# M307.net
KiCad netlist of a schematic drawn in EAGLE
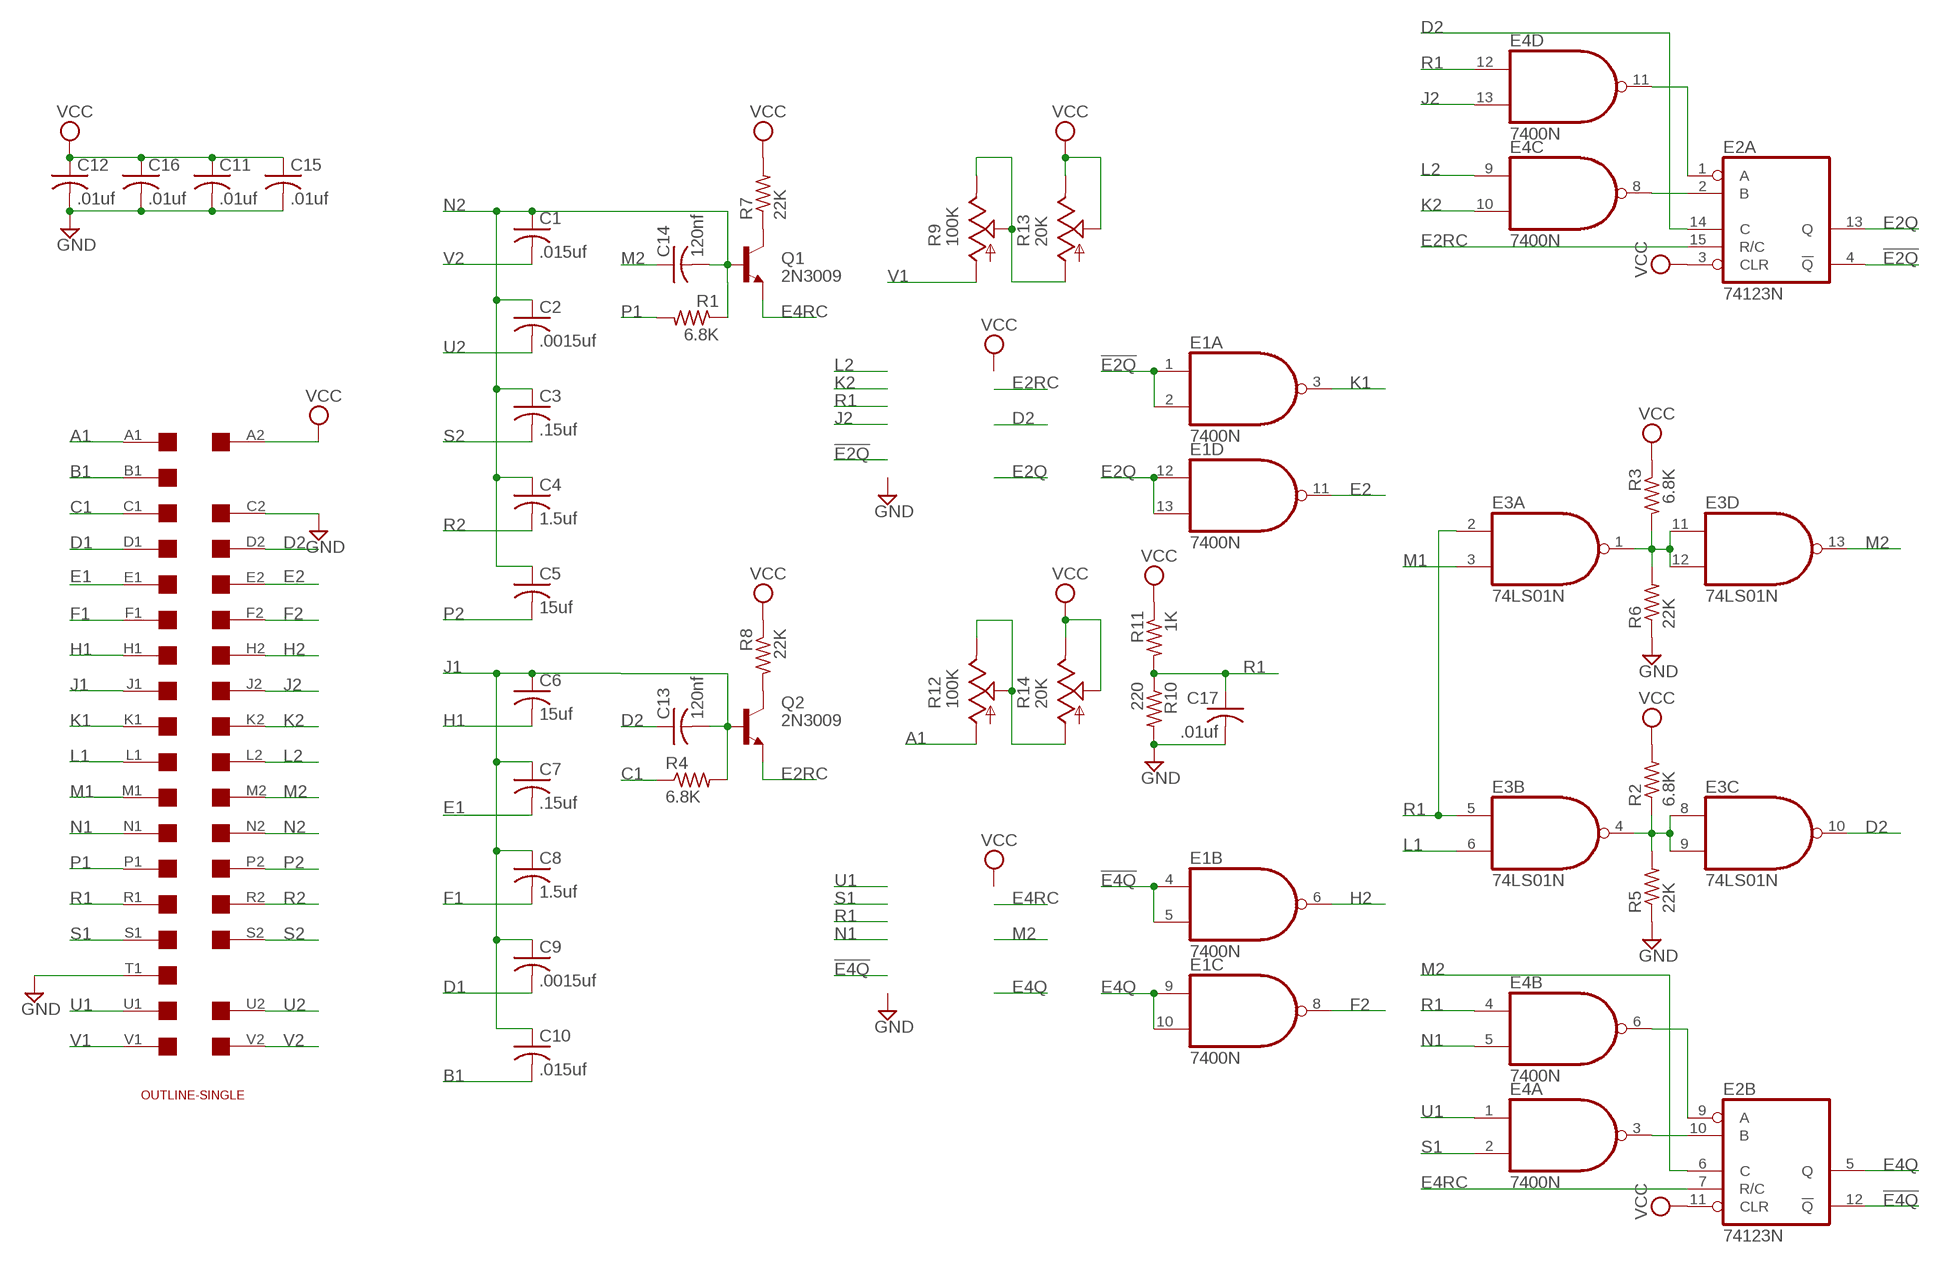
[diagram p0: schematic, sheet 1]

(export (version "E")
  (design (tool "Eeschema 10.0.6"))
  (components
    (comp (ref "C1")
      (value ".015uf")
      (footprint "eagle-import:C150-054X183")
      (libsource (lib "eagle-import") (part "C-US150-054X183"))
    )
    (comp (ref "C2")
      (value ".0015uf")
      (footprint "eagle-import:C050-025X075")
      (libsource (lib "eagle-import") (part "C-US050-025X075"))
    )
    (comp (ref "C3")
      (value ".15uf")
      (footprint "eagle-import:C102-043X133")
      (libsource (lib "eagle-import") (part "C-US102-043X133"))
    )
    (comp (ref "C4")
      (value "1.5uf")
      (footprint "eagle-import:C150-054X183")
      (libsource (lib "eagle-import") (part "C-US150-054X183"))
    )
    (comp (ref "C5")
      (value "15uf")
      (footprint "eagle-import:C150-054X183")
      (libsource (lib "eagle-import") (part "C-US150-054X183"))
    )
    (comp (ref "C6")
      (value "15uf")
      (footprint "eagle-import:C150-054X183")
      (libsource (lib "eagle-import") (part "C-US150-054X183"))
    )
    (comp (ref "C7")
      (value ".15uf")
      (footprint "eagle-import:C102-043X133")
      (libsource (lib "eagle-import") (part "C-US102-043X133"))
    )
    (comp (ref "C8")
      (value "1.5uf")
      (footprint "eagle-import:C150-054X183")
      (libsource (lib "eagle-import") (part "C-US150-054X183"))
    )
    (comp (ref "C9")
      (value ".0015uf")
      (footprint "eagle-import:C050-025X075")
      (libsource (lib "eagle-import") (part "C-US050-025X075"))
    )
    (comp (ref "C10")
      (value ".015uf")
      (footprint "eagle-import:C150-054X183")
      (libsource (lib "eagle-import") (part "C-US150-054X183"))
    )
    (comp (ref "C11")
      (value ".01uf")
      (footprint "eagle-import:C050-025X075")
      (libsource (lib "eagle-import") (part "C-US050-025X075"))
    )
    (comp (ref "C12")
      (value ".01uf")
      (footprint "eagle-import:C050-025X075")
      (libsource (lib "eagle-import") (part "C-US050-025X075"))
    )
    (comp (ref "C13")
      (value "120nf")
      (footprint "eagle-import:C075-032X103")
      (libsource (lib "eagle-import") (part "C-US075-032X103"))
    )
    (comp (ref "C14")
      (value "120nf")
      (footprint "eagle-import:C075-032X103")
      (libsource (lib "eagle-import") (part "C-US075-032X103"))
    )
    (comp (ref "C15")
      (value ".01uf")
      (footprint "eagle-import:C050-025X075")
      (libsource (lib "eagle-import") (part "C-US050-025X075"))
    )
    (comp (ref "C16")
      (value ".01uf")
      (footprint "eagle-import:C050-025X075")
      (libsource (lib "eagle-import") (part "C-US050-025X075"))
    )
    (comp (ref "C17")
      (value ".01uf")
      (footprint "eagle-import:C050-025X075")
      (libsource (lib "eagle-import") (part "C-US050-025X075"))
    )
    (comp (ref "E1")
      (value "7400N")
      (footprint "eagle-import:DIL14")
      (libsource (lib "eagle-import") (part "7400N"))
    )
    (comp (ref "E2")
      (value "74123N")
      (footprint "eagle-import:DIL16")
      (libsource (lib "eagle-import") (part "74123N"))
    )
    (comp (ref "E3")
      (value "74LS01N")
      (footprint "eagle-import:DIL14")
      (libsource (lib "eagle-import") (part "7401NLS"))
    )
    (comp (ref "E4")
      (value "7400N")
      (footprint "eagle-import:DIL14")
      (libsource (lib "eagle-import") (part "7400N"))
    )
    (comp (ref "Q1")
      (value "2N3009")
      (footprint "eagle-import:TO39")
      (libsource (lib "eagle-import") (part "-NPN-TO39-EBC2N3019"))
    )
    (comp (ref "Q2")
      (value "2N3009")
      (footprint "eagle-import:TO39")
      (libsource (lib "eagle-import") (part "-NPN-TO39-EBC2N3019"))
    )
    (comp (ref "R1")
      (value "6.8K")
      (footprint "eagle-import:0207_10")
      (libsource (lib "eagle-import") (part "R-US_0207/10"))
    )
    (comp (ref "R2")
      (value "6.8K")
      (footprint "eagle-import:0207_10")
      (libsource (lib "eagle-import") (part "R-US_0207/10"))
    )
    (comp (ref "R3")
      (value "6.8K")
      (footprint "eagle-import:0207_10")
      (libsource (lib "eagle-import") (part "R-US_0207/10"))
    )
    (comp (ref "R4")
      (value "6.8K")
      (footprint "eagle-import:0207_10")
      (libsource (lib "eagle-import") (part "R-US_0207/10"))
    )
    (comp (ref "R5")
      (value "22K")
      (footprint "eagle-import:0207_10")
      (libsource (lib "eagle-import") (part "R-US_0207/10"))
    )
    (comp (ref "R6")
      (value "22K")
      (footprint "eagle-import:0207_10")
      (libsource (lib "eagle-import") (part "R-US_0207/10"))
    )
    (comp (ref "R7")
      (value "22K")
      (footprint "eagle-import:0207_10")
      (libsource (lib "eagle-import") (part "R-US_0207/10"))
    )
    (comp (ref "R8")
      (value "22K")
      (footprint "eagle-import:0207_10")
      (libsource (lib "eagle-import") (part "R-US_0207/10"))
    )
    (comp (ref "R9")
      (value "100K")
      (footprint "eagle-import:PT-SPIN")
      (libsource (lib "eagle-import") (part "TRIM_US-PTSPIN"))
    )
    (comp (ref "R10")
      (value "220")
      (footprint "eagle-import:0207_10")
      (libsource (lib "eagle-import") (part "R-US_0207/10"))
    )
    (comp (ref "R11")
      (value "1K")
      (footprint "eagle-import:0207_10")
      (libsource (lib "eagle-import") (part "R-US_0207/10"))
    )
    (comp (ref "R12")
      (value "100K")
      (footprint "eagle-import:PT-SPIN")
      (libsource (lib "eagle-import") (part "TRIM_US-PTSPIN"))
    )
    (comp (ref "R13")
      (value "20K")
      (footprint "eagle-import:PT-SPIN")
      (libsource (lib "eagle-import") (part "TRIM_US-PTSPIN"))
    )
    (comp (ref "R14")
      (value "20K")
      (footprint "eagle-import:PT-SPIN")
      (libsource (lib "eagle-import") (part "TRIM_US-PTSPIN"))
    )
    (comp (ref "U$1")
      (value "SINGLE")
      (footprint "eagle-import:EDGE-CON2")
      (libsource (lib "eagle-import") (part "SINGLE"))
    )
    (comp (ref "U$4")
      (value "OUTLINE-SINGLE")
      (footprint "eagle-import:SINGLE")
      (libsource (lib "eagle-import") (part "OUTLINE-SINGLE"))
    )
  )
  (nets
    (net (code "1") (name "/A1") (class "Default")
      (node (ref "R12") (pin "A") (pinfunction "A_A") (pintype "passive"))
      (node (ref "U$1") (pin "A1") (pinfunction "1_A1") (pintype "bidirectional"))
    )
    (net (code "2") (name "/B1") (class "Default")
      (node (ref "C10") (pin "2") (pinfunction "2_2") (pintype "passive"))
      (node (ref "U$1") (pin "B1") (pinfunction "1_B1") (pintype "bidirectional"))
    )
    (net (code "3") (name "/C1") (class "Default")
      (node (ref "R4") (pin "1") (pinfunction "1_1") (pintype "passive"))
      (node (ref "U$1") (pin "C1") (pinfunction "1_C1") (pintype "bidirectional"))
    )
    (net (code "4") (name "/D1") (class "Default")
      (node (ref "C9") (pin "2") (pinfunction "2_2") (pintype "passive"))
      (node (ref "U$1") (pin "D1") (pinfunction "1_D1") (pintype "bidirectional"))
    )
    (net (code "5") (name "/D2") (class "Default")
      (node (ref "C13") (pin "1") (pinfunction "1_1") (pintype "passive"))
      (node (ref "E2") (pin "14") (pinfunction "C_14") (pintype "input"))
      (node (ref "E3") (pin "10") (pinfunction "O_10") (pintype "open_collector"))
      (node (ref "U$1") (pin "D2") (pinfunction "1_D2") (pintype "bidirectional"))
    )
    (net (code "6") (name "/E1") (class "Default")
      (node (ref "C7") (pin "2") (pinfunction "2_2") (pintype "passive"))
      (node (ref "U$1") (pin "E1") (pinfunction "1_E1") (pintype "bidirectional"))
    )
    (net (code "7") (name "/E2") (class "Default")
      (node (ref "E1") (pin "11") (pinfunction "O_11") (pintype "output"))
      (node (ref "U$1") (pin "E2") (pinfunction "1_E2") (pintype "bidirectional"))
    )
    (net (code "8") (name "/E2Q") (class "Default")
      (node (ref "E1") (pin "12") (pinfunction "I0_12") (pintype "input"))
      (node (ref "E1") (pin "13") (pinfunction "I1_13") (pintype "input"))
      (node (ref "E2") (pin "13") (pinfunction "Q_13") (pintype "output"))
    )
    (net (code "9") (name "/E2RC") (class "Default")
      (node (ref "E2") (pin "15") (pinfunction "R/C_15") (pintype "input"))
      (node (ref "Q2") (pin "1") (pinfunction "E_1") (pintype "passive"))
    )
    (net (code "10") (name "/E4Q") (class "Default")
      (node (ref "E1") (pin "10") (pinfunction "I1_10") (pintype "input"))
      (node (ref "E1") (pin "9") (pinfunction "I0_9") (pintype "input"))
      (node (ref "E2") (pin "5") (pinfunction "Q_5") (pintype "output"))
    )
    (net (code "11") (name "/E4RC") (class "Default")
      (node (ref "E2") (pin "7") (pinfunction "R/C_7") (pintype "input"))
      (node (ref "Q1") (pin "1") (pinfunction "E_1") (pintype "passive"))
    )
    (net (code "12") (name "/F1") (class "Default")
      (node (ref "C8") (pin "2") (pinfunction "2_2") (pintype "passive"))
      (node (ref "U$1") (pin "F1") (pinfunction "1_F1") (pintype "bidirectional"))
    )
    (net (code "13") (name "/F2") (class "Default")
      (node (ref "E1") (pin "8") (pinfunction "O_8") (pintype "output"))
      (node (ref "U$1") (pin "F2") (pinfunction "1_F2") (pintype "bidirectional"))
    )
    (net (code "14") (name "/H1") (class "Default")
      (node (ref "C6") (pin "2") (pinfunction "2_2") (pintype "passive"))
      (node (ref "U$1") (pin "H1") (pinfunction "1_H1") (pintype "bidirectional"))
    )
    (net (code "15") (name "/H2") (class "Default")
      (node (ref "E1") (pin "6") (pinfunction "O_6") (pintype "output"))
      (node (ref "U$1") (pin "H2") (pinfunction "1_H2") (pintype "bidirectional"))
    )
    (net (code "16") (name "/J1") (class "Default")
      (node (ref "C10") (pin "1") (pinfunction "1_1") (pintype "passive"))
      (node (ref "C13") (pin "2") (pinfunction "2_2") (pintype "passive"))
      (node (ref "C6") (pin "1") (pinfunction "1_1") (pintype "passive"))
      (node (ref "C7") (pin "1") (pinfunction "1_1") (pintype "passive"))
      (node (ref "C8") (pin "1") (pinfunction "1_1") (pintype "passive"))
      (node (ref "C9") (pin "1") (pinfunction "1_1") (pintype "passive"))
      (node (ref "Q2") (pin "2") (pinfunction "B_2") (pintype "passive"))
      (node (ref "R4") (pin "2") (pinfunction "2_2") (pintype "passive"))
      (node (ref "U$1") (pin "J1") (pinfunction "1_J1") (pintype "bidirectional"))
    )
    (net (code "17") (name "/J2") (class "Default")
      (node (ref "E4") (pin "13") (pinfunction "I1_13") (pintype "input"))
      (node (ref "U$1") (pin "J2") (pinfunction "1_J2") (pintype "bidirectional"))
    )
    (net (code "18") (name "/K1") (class "Default")
      (node (ref "E1") (pin "3") (pinfunction "O_3") (pintype "output"))
      (node (ref "U$1") (pin "K1") (pinfunction "1_K1") (pintype "bidirectional"))
    )
    (net (code "19") (name "/K2") (class "Default")
      (node (ref "E4") (pin "10") (pinfunction "I1_10") (pintype "input"))
      (node (ref "U$1") (pin "K2") (pinfunction "1_K2") (pintype "bidirectional"))
    )
    (net (code "20") (name "/L1") (class "Default")
      (node (ref "E3") (pin "6") (pinfunction "I1_6") (pintype "input"))
      (node (ref "U$1") (pin "L1") (pinfunction "1_L1") (pintype "bidirectional"))
    )
    (net (code "21") (name "/L2") (class "Default")
      (node (ref "E4") (pin "9") (pinfunction "I0_9") (pintype "input"))
      (node (ref "U$1") (pin "L2") (pinfunction "1_L2") (pintype "bidirectional"))
    )
    (net (code "22") (name "/M1") (class "Default")
      (node (ref "E3") (pin "3") (pinfunction "I1_3") (pintype "input"))
      (node (ref "U$1") (pin "M1") (pinfunction "1_M1") (pintype "bidirectional"))
    )
    (net (code "23") (name "/M2") (class "Default")
      (node (ref "C14") (pin "1") (pinfunction "1_1") (pintype "passive"))
      (node (ref "E2") (pin "6") (pinfunction "C_6") (pintype "input"))
      (node (ref "E3") (pin "13") (pinfunction "O_13") (pintype "open_collector"))
      (node (ref "U$1") (pin "M2") (pinfunction "1_M2") (pintype "bidirectional"))
    )
    (net (code "24") (name "/N1") (class "Default")
      (node (ref "E4") (pin "5") (pinfunction "I1_5") (pintype "input"))
      (node (ref "U$1") (pin "N1") (pinfunction "1_N1") (pintype "bidirectional"))
    )
    (net (code "25") (name "/N2") (class "Default")
      (node (ref "C1") (pin "1") (pinfunction "1_1") (pintype "passive"))
      (node (ref "C14") (pin "2") (pinfunction "2_2") (pintype "passive"))
      (node (ref "C2") (pin "1") (pinfunction "1_1") (pintype "passive"))
      (node (ref "C3") (pin "1") (pinfunction "1_1") (pintype "passive"))
      (node (ref "C4") (pin "1") (pinfunction "1_1") (pintype "passive"))
      (node (ref "C5") (pin "1") (pinfunction "1_1") (pintype "passive"))
      (node (ref "Q1") (pin "2") (pinfunction "B_2") (pintype "passive"))
      (node (ref "R1") (pin "1") (pinfunction "1_1") (pintype "passive"))
      (node (ref "U$1") (pin "N2") (pinfunction "1_N2") (pintype "bidirectional"))
    )
    (net (code "26") (name "/P1") (class "Default")
      (node (ref "R1") (pin "2") (pinfunction "2_2") (pintype "passive"))
      (node (ref "U$1") (pin "P1") (pinfunction "1_P1") (pintype "bidirectional"))
    )
    (net (code "27") (name "/P2") (class "Default")
      (node (ref "C5") (pin "2") (pinfunction "2_2") (pintype "passive"))
      (node (ref "U$1") (pin "P2") (pinfunction "1_P2") (pintype "bidirectional"))
    )
    (net (code "28") (name "/R1") (class "Default")
      (node (ref "C17") (pin "1") (pinfunction "1_1") (pintype "passive"))
      (node (ref "E3") (pin "2") (pinfunction "I0_2") (pintype "input"))
      (node (ref "E3") (pin "5") (pinfunction "I0_5") (pintype "input"))
      (node (ref "E4") (pin "12") (pinfunction "I0_12") (pintype "input"))
      (node (ref "E4") (pin "4") (pinfunction "I0_4") (pintype "input"))
      (node (ref "R10") (pin "1") (pinfunction "1_1") (pintype "passive"))
      (node (ref "R11") (pin "2") (pinfunction "2_2") (pintype "passive"))
      (node (ref "U$1") (pin "R1") (pinfunction "1_R1") (pintype "bidirectional"))
    )
    (net (code "29") (name "/R2") (class "Default")
      (node (ref "C4") (pin "2") (pinfunction "2_2") (pintype "passive"))
      (node (ref "U$1") (pin "R2") (pinfunction "1_R2") (pintype "bidirectional"))
    )
    (net (code "30") (name "/S1") (class "Default")
      (node (ref "E4") (pin "2") (pinfunction "I1_2") (pintype "input"))
      (node (ref "U$1") (pin "S1") (pinfunction "1_S1") (pintype "bidirectional"))
    )
    (net (code "31") (name "/S2") (class "Default")
      (node (ref "C3") (pin "2") (pinfunction "2_2") (pintype "passive"))
      (node (ref "U$1") (pin "S2") (pinfunction "1_S2") (pintype "bidirectional"))
    )
    (net (code "32") (name "/U1") (class "Default")
      (node (ref "E4") (pin "1") (pinfunction "I0_1") (pintype "input"))
      (node (ref "U$1") (pin "U1") (pinfunction "1_U1") (pintype "bidirectional"))
    )
    (net (code "33") (name "/U2") (class "Default")
      (node (ref "C2") (pin "2") (pinfunction "2_2") (pintype "passive"))
      (node (ref "U$1") (pin "U2") (pinfunction "1_U2") (pintype "bidirectional"))
    )
    (net (code "34") (name "/V1") (class "Default")
      (node (ref "R9") (pin "A") (pinfunction "A_A") (pintype "passive"))
      (node (ref "U$1") (pin "V1") (pinfunction "1_V1") (pintype "bidirectional"))
    )
    (net (code "35") (name "/V2") (class "Default")
      (node (ref "C1") (pin "2") (pinfunction "2_2") (pintype "passive"))
      (node (ref "U$1") (pin "V2") (pinfunction "1_V2") (pintype "bidirectional"))
    )
    (net (code "36") (name "/~{E2Q}") (class "Default")
      (node (ref "E1") (pin "1") (pinfunction "I0_1") (pintype "input"))
      (node (ref "E1") (pin "2") (pinfunction "I1_2") (pintype "input"))
      (node (ref "E2") (pin "4") (pinfunction "~{Q}_4") (pintype "output"))
    )
    (net (code "37") (name "/~{E4Q}") (class "Default")
      (node (ref "E1") (pin "4") (pinfunction "I0_4") (pintype "input"))
      (node (ref "E1") (pin "5") (pinfunction "I1_5") (pintype "input"))
      (node (ref "E2") (pin "12") (pinfunction "~{Q}_12") (pintype "output"))
    )
    (net (code "38") (name "GND") (class "Default")
      (node (ref "C11") (pin "2") (pinfunction "2_2") (pintype "passive"))
      (node (ref "C12") (pin "2") (pinfunction "2_2") (pintype "passive"))
      (node (ref "C15") (pin "2") (pinfunction "2_2") (pintype "passive"))
      (node (ref "C16") (pin "2") (pinfunction "2_2") (pintype "passive"))
      (node (ref "C17") (pin "2") (pinfunction "2_2") (pintype "passive"))
      (node (ref "R10") (pin "2") (pinfunction "2_2") (pintype "passive"))
      (node (ref "R5") (pin "1") (pinfunction "1_1") (pintype "passive"))
      (node (ref "R6") (pin "1") (pinfunction "1_1") (pintype "passive"))
      (node (ref "U$1") (pin "C2") (pinfunction "1_C2") (pintype "bidirectional"))
      (node (ref "U$1") (pin "T1") (pinfunction "1_T1") (pintype "bidirectional"))
    )
    (net (code "39") (name "Net-(E2A-A)") (class "Default")
      (node (ref "E2") (pin "1") (pinfunction "A_1") (pintype "input"))
      (node (ref "E4") (pin "11") (pinfunction "O_11") (pintype "output"))
    )
    (net (code "40") (name "Net-(E2A-B)") (class "Default")
      (node (ref "E2") (pin "2") (pinfunction "B_2") (pintype "input"))
      (node (ref "E4") (pin "8") (pinfunction "O_8") (pintype "output"))
    )
    (net (code "41") (name "Net-(E2B-A)") (class "Default")
      (node (ref "E2") (pin "9") (pinfunction "A_9") (pintype "input"))
      (node (ref "E4") (pin "6") (pinfunction "O_6") (pintype "output"))
    )
    (net (code "42") (name "Net-(E2B-B)") (class "Default")
      (node (ref "E2") (pin "10") (pinfunction "B_10") (pintype "input"))
      (node (ref "E4") (pin "3") (pinfunction "O_3") (pintype "output"))
    )
    (net (code "43") (name "Net-(E3A-O)") (class "Default")
      (node (ref "E3") (pin "1") (pinfunction "O_1") (pintype "open_collector"))
      (node (ref "E3") (pin "11") (pinfunction "I0_11") (pintype "input"))
      (node (ref "E3") (pin "12") (pinfunction "I1_12") (pintype "input"))
      (node (ref "R3") (pin "2") (pinfunction "2_2") (pintype "passive"))
      (node (ref "R6") (pin "2") (pinfunction "2_2") (pintype "passive"))
    )
    (net (code "44") (name "Net-(E3B-O)") (class "Default")
      (node (ref "E3") (pin "4") (pinfunction "O_4") (pintype "open_collector"))
      (node (ref "E3") (pin "8") (pinfunction "I0_8") (pintype "input"))
      (node (ref "E3") (pin "9") (pinfunction "I1_9") (pintype "input"))
      (node (ref "R2") (pin "1") (pinfunction "1_1") (pintype "passive"))
      (node (ref "R5") (pin "2") (pinfunction "2_2") (pintype "passive"))
    )
    (net (code "45") (name "Net-(Q1-C)") (class "Default")
      (node (ref "Q1") (pin "3") (pinfunction "C_3") (pintype "passive"))
      (node (ref "R7") (pin "1") (pinfunction "1_1") (pintype "passive"))
    )
    (net (code "46") (name "Net-(Q2-C)") (class "Default")
      (node (ref "Q2") (pin "3") (pinfunction "C_3") (pintype "passive"))
      (node (ref "R8") (pin "2") (pinfunction "2_2") (pintype "passive"))
    )
    (net (code "47") (name "Net-(R12-PadE)") (class "Default")
      (node (ref "R12") (pin "E") (pinfunction "E_E") (pintype "passive"))
      (node (ref "R12") (pin "S") (pinfunction "S_S") (pintype "passive"))
      (node (ref "R14") (pin "A") (pinfunction "A_A") (pintype "passive"))
    )
    (net (code "48") (name "Net-(R13-PadA)") (class "Default")
      (node (ref "R13") (pin "A") (pinfunction "A_A") (pintype "passive"))
      (node (ref "R9") (pin "E") (pinfunction "E_E") (pintype "passive"))
      (node (ref "R9") (pin "S") (pinfunction "S_S") (pintype "passive"))
    )
    (net (code "49") (name "VCC") (class "Default")
      (node (ref "C11") (pin "1") (pinfunction "1_1") (pintype "passive"))
      (node (ref "C12") (pin "1") (pinfunction "1_1") (pintype "passive"))
      (node (ref "C15") (pin "1") (pinfunction "1_1") (pintype "passive"))
      (node (ref "C16") (pin "1") (pinfunction "1_1") (pintype "passive"))
      (node (ref "E2") (pin "11") (pinfunction "CLR_11") (pintype "input"))
      (node (ref "E2") (pin "3") (pinfunction "CLR_3") (pintype "input"))
      (node (ref "R11") (pin "1") (pinfunction "1_1") (pintype "passive"))
      (node (ref "R13") (pin "E") (pinfunction "E_E") (pintype "passive"))
      (node (ref "R13") (pin "S") (pinfunction "S_S") (pintype "passive"))
      (node (ref "R14") (pin "E") (pinfunction "E_E") (pintype "passive"))
      (node (ref "R14") (pin "S") (pinfunction "S_S") (pintype "passive"))
      (node (ref "R2") (pin "2") (pinfunction "2_2") (pintype "passive"))
      (node (ref "R3") (pin "1") (pinfunction "1_1") (pintype "passive"))
      (node (ref "R7") (pin "2") (pinfunction "2_2") (pintype "passive"))
      (node (ref "R8") (pin "1") (pinfunction "1_1") (pintype "passive"))
      (node (ref "U$1") (pin "A2") (pinfunction "1_A2") (pintype "bidirectional"))
    )
  )
)
